# Main_board.net
KiCad netlist of a schematic drawn in EAGLE
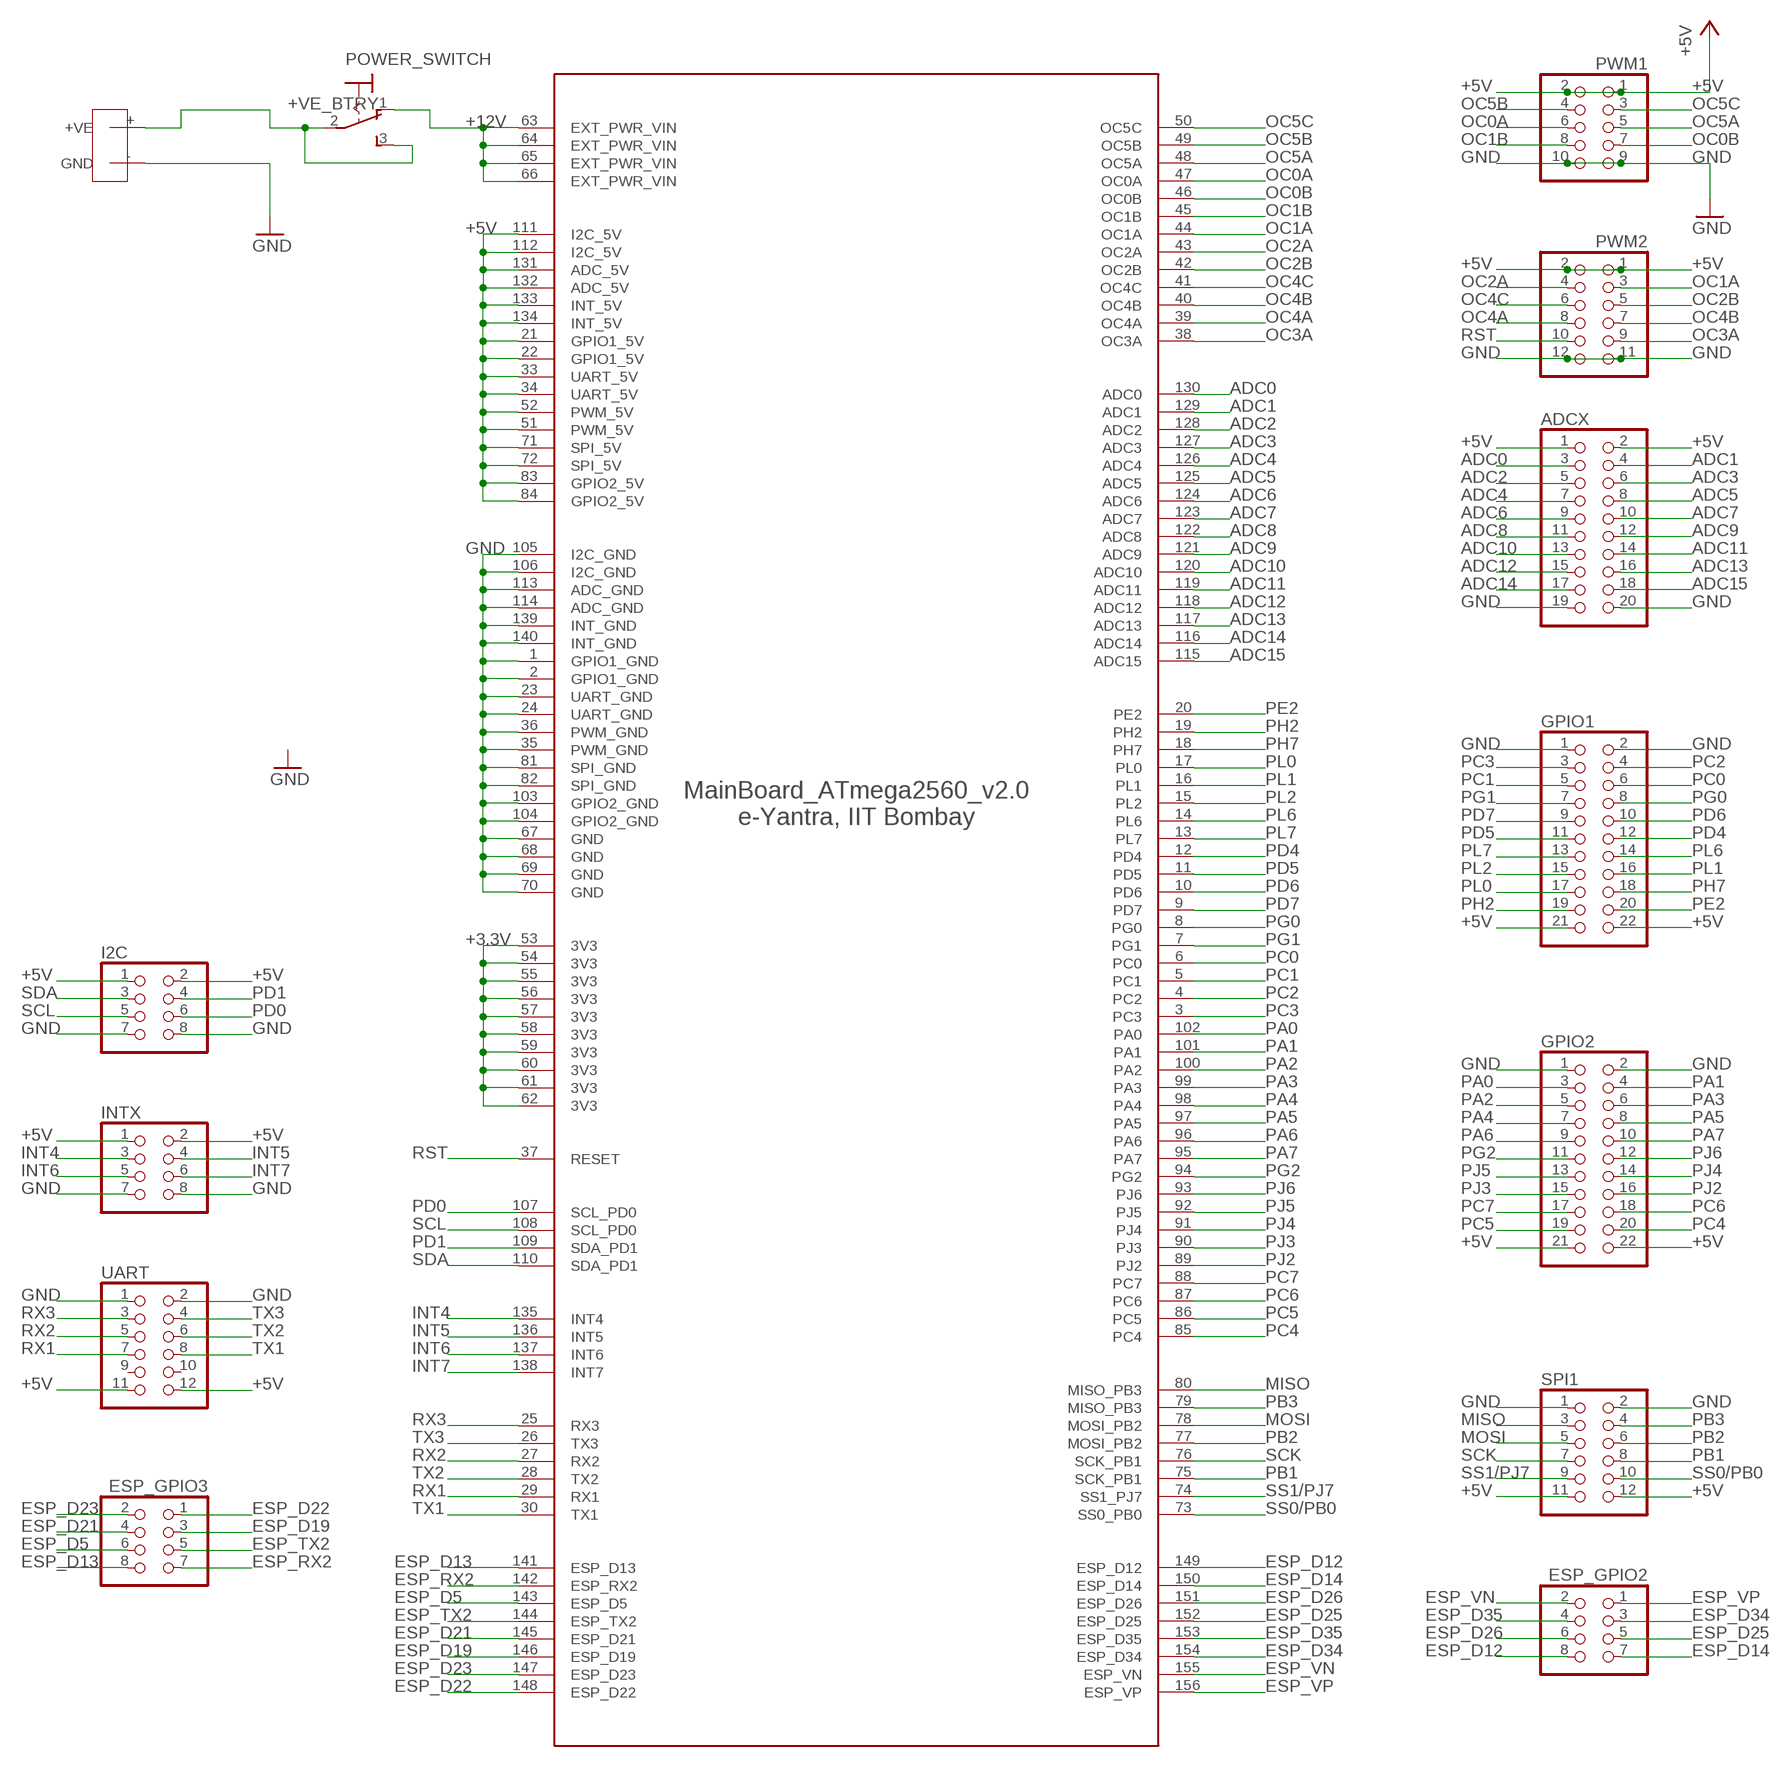
[diagram p0: schematic, sheet 1]
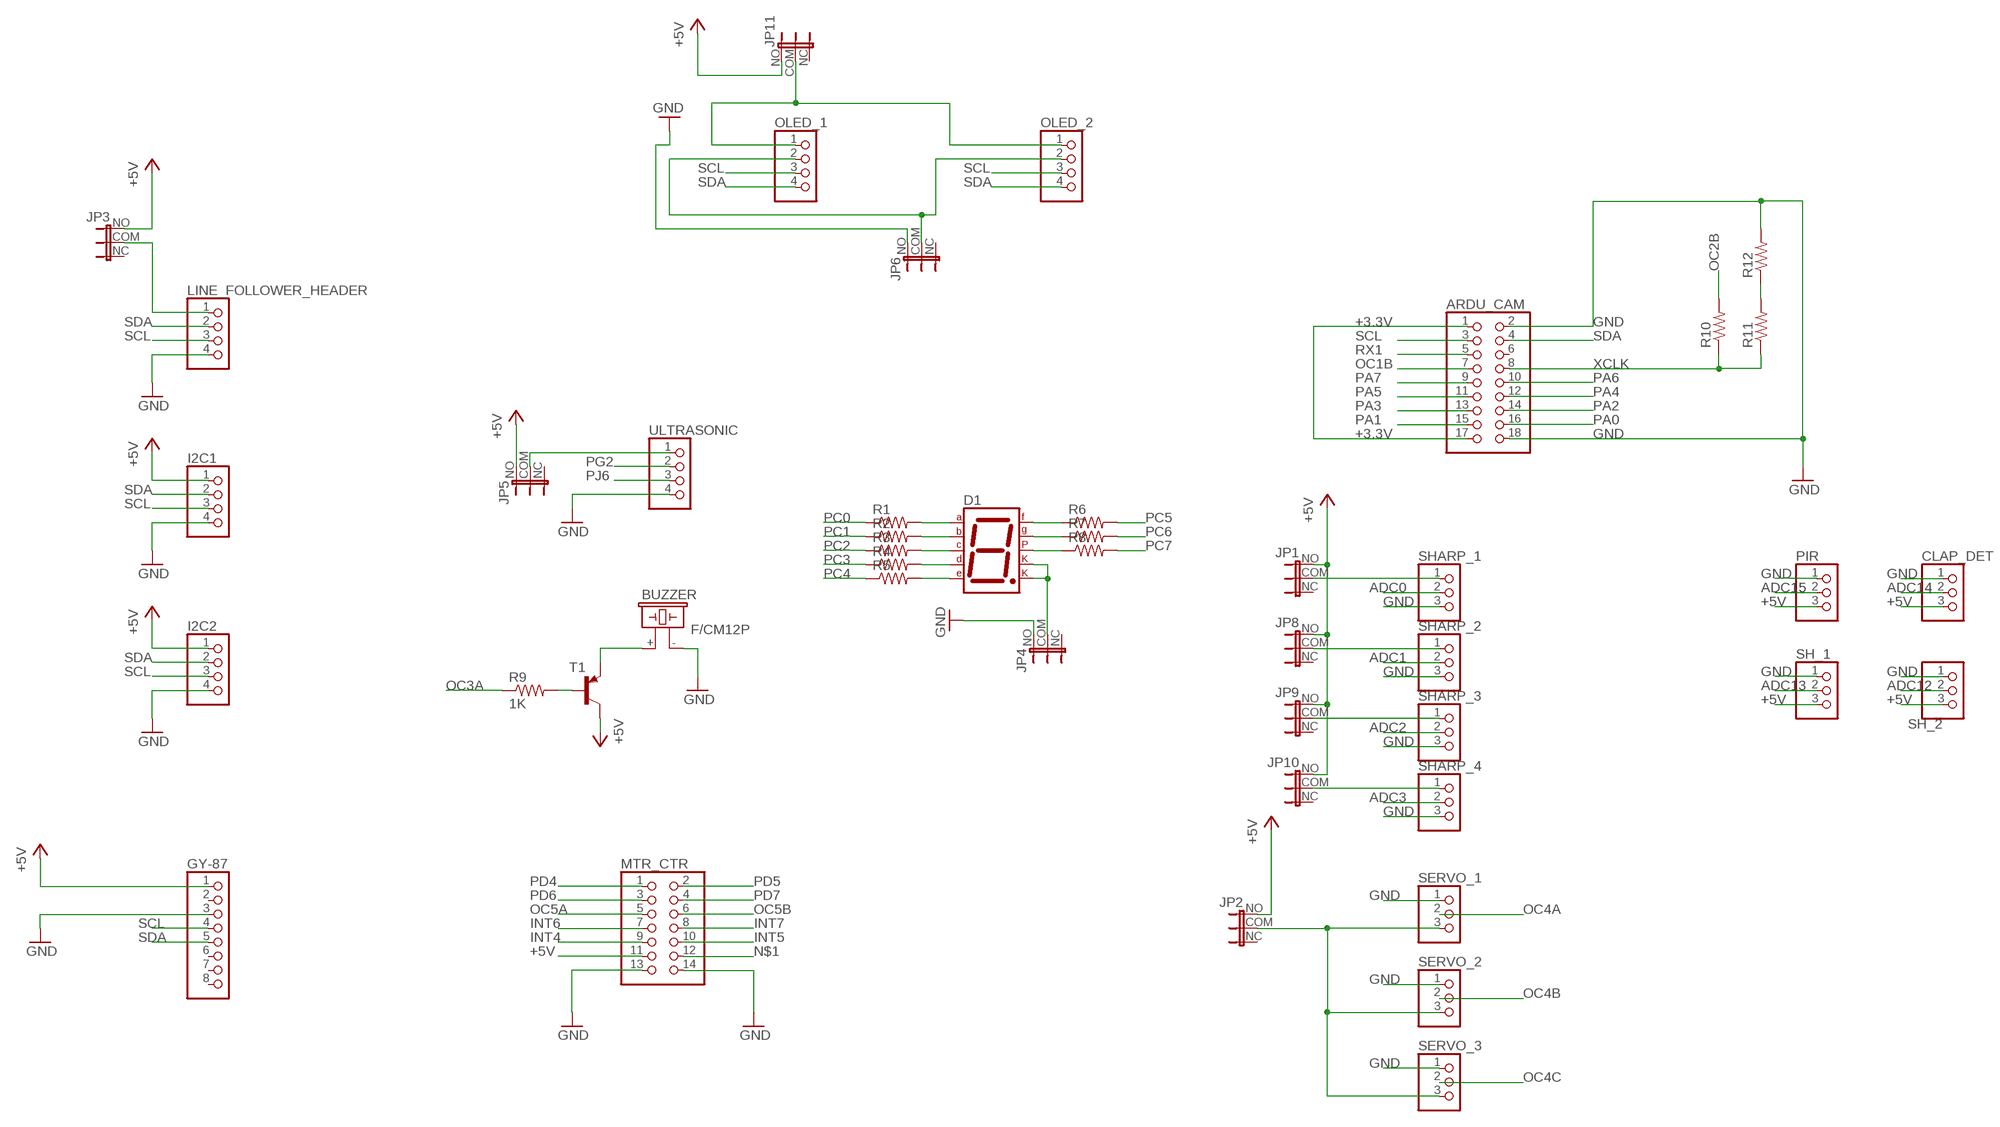
[diagram p1: schematic, sheet 2]

(export (version "E")
  (design (tool "Eeschema 10.0.6"))
  (components
    (comp (ref "ADCX")
      (value "PINHD-2X10")
      (footprint "eagle-import:2X10")
      (libsource (lib "eagle-import") (part "PINHD-2X10"))
    )
    (comp (ref "ESP_GPIO2")
      (value "PINHD-2X4")
      (footprint "eagle-import:2X04")
      (libsource (lib "eagle-import") (part "PINHD-2X4"))
    )
    (comp (ref "ESP_GPIO3")
      (value "PINHD-2X4")
      (footprint "eagle-import:2X04")
      (libsource (lib "eagle-import") (part "PINHD-2X4"))
    )
    (comp (ref "EYFI_MEGA")
      (value "ATMEGA2560_V2.0")
      (footprint "eagle-import:ATMEGA2560_V2.0")
      (libsource (lib "eagle-import") (part "ATMEGA2560_V2.0"))
    )
    (comp (ref "GPIO1")
      (value "PINHD-2X11")
      (footprint "eagle-import:2X11")
      (libsource (lib "eagle-import") (part "PINHD-2X11"))
    )
    (comp (ref "GPIO2")
      (value "PINHD-2X11")
      (footprint "eagle-import:2X11")
      (libsource (lib "eagle-import") (part "PINHD-2X11"))
    )
    (comp (ref "I2C")
      (value "PINHD-2X4")
      (footprint "eagle-import:2X04")
      (libsource (lib "eagle-import") (part "PINHD-2X4"))
    )
    (comp (ref "INTX")
      (value "PINHD-2X4")
      (footprint "eagle-import:2X04")
      (libsource (lib "eagle-import") (part "PINHD-2X4"))
    )
    (comp (ref "POWER_SWITCH")
      (value "M9040P")
      (footprint "eagle-import:M9040P")
      (libsource (lib "eagle-import") (part "M9040P"))
    )
    (comp (ref "PWM1")
      (value "PINHD-2X5")
      (footprint "eagle-import:2X05")
      (libsource (lib "eagle-import") (part "PINHD-2X5"))
    )
    (comp (ref "PWM2")
      (value "PINHD-2X6")
      (footprint "eagle-import:2X06")
      (libsource (lib "eagle-import") (part "PINHD-2X6"))
    )
    (comp (ref "SPI1")
      (value "PINHD-2X6")
      (footprint "eagle-import:2X06")
      (libsource (lib "eagle-import") (part "PINHD-2X6"))
    )
    (comp (ref "U$1")
      (value "DEANS")
      (footprint "eagle-import:DEANS")
      (libsource (lib "eagle-import") (part "DEANS"))
    )
    (comp (ref "UART")
      (value "PINHD-2X6")
      (footprint "eagle-import:2X06")
      (libsource (lib "eagle-import") (part "PINHD-2X6"))
    )
    (comp (ref "ARDU_CAM")
      (value "PINHD-2X9")
      (footprint "eagle-import:2X09")
      (libsource (lib "eagle-import") (part "PINHD-2X9"))
    )
    (comp (ref "BUZZER")
      (value "F/CM12P")
      (footprint "eagle-import:F_CM12P")
      (libsource (lib "eagle-import") (part "F/CM12P"))
    )
    (comp (ref "CLAP_DET")
      (value "PINHD-1X3")
      (footprint "eagle-import:1X03")
      (libsource (lib "eagle-import") (part "pinhead_325_PINHD-1X3"))
    )
    (comp (ref "D1")
      (value "7SEG-CK")
      (footprint "eagle-import:7SEG-13")
      (libsource (lib "eagle-import") (part "7SEG-CK"))
    )
    (comp (ref "GY-87")
      (value "PINHD-1X8")
      (footprint "eagle-import:1X08")
      (libsource (lib "eagle-import") (part "PINHD-1X8"))
    )
    (comp (ref "I2C1")
      (value "PINHD-1X4")
      (footprint "eagle-import:1X04")
      (libsource (lib "eagle-import") (part "PINHD-1X4"))
    )
    (comp (ref "I2C2")
      (value "PINHD-1X4")
      (footprint "eagle-import:1X04")
      (libsource (lib "eagle-import") (part "PINHD-1X4"))
    )
    (comp (ref "JP1")
      (value "JP2E")
      (footprint "eagle-import:JP2")
      (libsource (lib "eagle-import") (part "JP2E"))
    )
    (comp (ref "JP2")
      (value "JP2E")
      (footprint "eagle-import:JP2")
      (libsource (lib "eagle-import") (part "JP2E"))
    )
    (comp (ref "JP3")
      (value "JP2E")
      (footprint "eagle-import:JP2")
      (libsource (lib "eagle-import") (part "JP2E"))
    )
    (comp (ref "JP4")
      (value "JP2E")
      (footprint "eagle-import:JP2")
      (libsource (lib "eagle-import") (part "JP2E"))
    )
    (comp (ref "JP5")
      (value "JP2E")
      (footprint "eagle-import:JP2")
      (libsource (lib "eagle-import") (part "JP2E"))
    )
    (comp (ref "JP6")
      (value "JP2E")
      (footprint "eagle-import:JP2")
      (libsource (lib "eagle-import") (part "JP2E"))
    )
    (comp (ref "JP8")
      (value "JP2E")
      (footprint "eagle-import:JP2")
      (libsource (lib "eagle-import") (part "JP2E"))
    )
    (comp (ref "JP9")
      (value "JP2E")
      (footprint "eagle-import:JP2")
      (libsource (lib "eagle-import") (part "JP2E"))
    )
    (comp (ref "JP10")
      (value "JP2E")
      (footprint "eagle-import:JP2")
      (libsource (lib "eagle-import") (part "JP2E"))
    )
    (comp (ref "JP11")
      (value "JP2E")
      (footprint "eagle-import:JP2")
      (libsource (lib "eagle-import") (part "JP2E"))
    )
    (comp (ref "LINE_FOLLOWER_HEADER")
      (value "PINHD-1X4")
      (footprint "eagle-import:1X04")
      (libsource (lib "eagle-import") (part "PINHD-1X4"))
    )
    (comp (ref "MTR_CTR")
      (value "PINHD-2X7")
      (footprint "eagle-import:2X07")
      (libsource (lib "eagle-import") (part "PINHD-2X7"))
    )
    (comp (ref "OLED_1")
      (value "PINHD-1X4")
      (footprint "eagle-import:1X04")
      (libsource (lib "eagle-import") (part "PINHD-1X4"))
    )
    (comp (ref "OLED_2")
      (value "PINHD-1X4")
      (footprint "eagle-import:1X04")
      (libsource (lib "eagle-import") (part "PINHD-1X4"))
    )
    (comp (ref "PIR")
      (value "PINHD-1X3")
      (footprint "eagle-import:1X03")
      (libsource (lib "eagle-import") (part "pinhead_325_PINHD-1X3"))
    )
    (comp (ref "R1")
      (value "R-US_R1206")
      (footprint "eagle-import:R1206")
      (libsource (lib "eagle-import") (part "R-US_R1206"))
    )
    (comp (ref "R2")
      (value "R-US_R1206")
      (footprint "eagle-import:R1206")
      (libsource (lib "eagle-import") (part "R-US_R1206"))
    )
    (comp (ref "R3")
      (value "R-US_R1206")
      (footprint "eagle-import:R1206")
      (libsource (lib "eagle-import") (part "R-US_R1206"))
    )
    (comp (ref "R4")
      (value "R-US_R1206")
      (footprint "eagle-import:R1206")
      (libsource (lib "eagle-import") (part "R-US_R1206"))
    )
    (comp (ref "R5")
      (value "R-US_R1206")
      (footprint "eagle-import:R1206")
      (libsource (lib "eagle-import") (part "R-US_R1206"))
    )
    (comp (ref "R6")
      (value "R-US_R1206")
      (footprint "eagle-import:R1206")
      (libsource (lib "eagle-import") (part "R-US_R1206"))
    )
    (comp (ref "R7")
      (value "R-US_R1206")
      (footprint "eagle-import:R1206")
      (libsource (lib "eagle-import") (part "R-US_R1206"))
    )
    (comp (ref "R8")
      (value "R-US_R1206")
      (footprint "eagle-import:R1206")
      (libsource (lib "eagle-import") (part "R-US_R1206"))
    )
    (comp (ref "R9")
      (value "1K")
      (footprint "eagle-import:R1206")
      (libsource (lib "eagle-import") (part "R-US_R1206"))
    )
    (comp (ref "R10")
      (value "R-US_R1206")
      (footprint "eagle-import:R1206")
      (libsource (lib "eagle-import") (part "R-US_R1206"))
    )
    (comp (ref "R11")
      (value "R-US_R1206")
      (footprint "eagle-import:R1206")
      (libsource (lib "eagle-import") (part "R-US_R1206"))
    )
    (comp (ref "R12")
      (value "R-US_R1206")
      (footprint "eagle-import:R1206")
      (libsource (lib "eagle-import") (part "R-US_R1206"))
    )
    (comp (ref "SERVO_1")
      (value "PINHD-1X3")
      (footprint "eagle-import:1X03")
      (libsource (lib "eagle-import") (part "pinhead_325_PINHD-1X3"))
    )
    (comp (ref "SERVO_2")
      (value "PINHD-1X3")
      (footprint "eagle-import:1X03")
      (libsource (lib "eagle-import") (part "pinhead_325_PINHD-1X3"))
    )
    (comp (ref "SERVO_3")
      (value "PINHD-1X3")
      (footprint "eagle-import:1X03")
      (libsource (lib "eagle-import") (part "pinhead_325_PINHD-1X3"))
    )
    (comp (ref "SHARP_1")
      (value "PINHD-1X3")
      (footprint "eagle-import:1X03")
      (libsource (lib "eagle-import") (part "PINHD-1X3"))
    )
    (comp (ref "SHARP_2")
      (value "PINHD-1X3")
      (footprint "eagle-import:1X03")
      (libsource (lib "eagle-import") (part "PINHD-1X3"))
    )
    (comp (ref "SHARP_3")
      (value "PINHD-1X3")
      (footprint "eagle-import:1X03")
      (libsource (lib "eagle-import") (part "PINHD-1X3"))
    )
    (comp (ref "SHARP_4")
      (value "PINHD-1X3")
      (footprint "eagle-import:1X03")
      (libsource (lib "eagle-import") (part "PINHD-1X3"))
    )
    (comp (ref "SH_1")
      (value "PINHD-1X3")
      (footprint "eagle-import:1X03")
      (libsource (lib "eagle-import") (part "pinhead_325_PINHD-1X3"))
    )
    (comp (ref "SH_2")
      (value "PINHD-1X3")
      (footprint "eagle-import:1X03")
      (libsource (lib "eagle-import") (part "pinhead_325_PINHD-1X3"))
    )
    (comp (ref "T1")
      (value "BC807-16-PNP-SOT23-BEC")
      (footprint "eagle-import:SOT23-BEC")
      (libsource (lib "eagle-import") (part "-PNP-SOT23-BECBC807-16"))
    )
    (comp (ref "ULTRASONIC")
      (value "PINHD-1X4")
      (footprint "eagle-import:1X04")
      (libsource (lib "eagle-import") (part "PINHD-1X4"))
    )
  )
  (nets
    (net (code "1") (name "+3.3V") (class "Default")
      (node (ref "ARDU_CAM") (pin "1") (pinfunction "1_1") (pintype "passive"))
      (node (ref "ARDU_CAM") (pin "17") (pinfunction "17_17") (pintype "passive"))
      (node (ref "EYFI_MEGA") (pin "53") (pinfunction "3V3_53") (pintype "power_in"))
      (node (ref "EYFI_MEGA") (pin "54") (pinfunction "3V3_54") (pintype "power_in"))
      (node (ref "EYFI_MEGA") (pin "55") (pinfunction "3V3_55") (pintype "power_in"))
      (node (ref "EYFI_MEGA") (pin "56") (pinfunction "3V3_56") (pintype "power_in"))
      (node (ref "EYFI_MEGA") (pin "57") (pinfunction "3V3_57") (pintype "power_in"))
      (node (ref "EYFI_MEGA") (pin "58") (pinfunction "3V3_58") (pintype "power_in"))
      (node (ref "EYFI_MEGA") (pin "59") (pinfunction "3V3_59") (pintype "power_in"))
      (node (ref "EYFI_MEGA") (pin "60") (pinfunction "3V3_60") (pintype "power_in"))
      (node (ref "EYFI_MEGA") (pin "61") (pinfunction "3V3_61") (pintype "power_in"))
      (node (ref "EYFI_MEGA") (pin "62") (pinfunction "3V3_62") (pintype "power_in"))
    )
    (net (code "2") (name "+5V") (class "Default")
      (node (ref "ADCX") (pin "1") (pinfunction "1_1") (pintype "passive"))
      (node (ref "ADCX") (pin "2") (pinfunction "2_2") (pintype "passive"))
      (node (ref "CLAP_DET") (pin "3") (pinfunction "3_3") (pintype "passive"))
      (node (ref "EYFI_MEGA") (pin "111") (pinfunction "I2C_5V_111") (pintype "power_in"))
      (node (ref "EYFI_MEGA") (pin "112") (pinfunction "I2C_5V_112") (pintype "power_in"))
      (node (ref "EYFI_MEGA") (pin "131") (pinfunction "ADC_5V_131") (pintype "power_in"))
      (node (ref "EYFI_MEGA") (pin "132") (pinfunction "ADC_5V_132") (pintype "power_in"))
      (node (ref "EYFI_MEGA") (pin "133") (pinfunction "INT_5V_133") (pintype "power_in"))
      (node (ref "EYFI_MEGA") (pin "134") (pinfunction "INT_5V_134") (pintype "power_in"))
      (node (ref "EYFI_MEGA") (pin "21") (pinfunction "GPIO1_5V_21") (pintype "power_in"))
      (node (ref "EYFI_MEGA") (pin "22") (pinfunction "GPIO1_5V_22") (pintype "power_in"))
      (node (ref "EYFI_MEGA") (pin "33") (pinfunction "UART_5V_33") (pintype "power_in"))
      (node (ref "EYFI_MEGA") (pin "34") (pinfunction "UART_5V_34") (pintype "power_in"))
      (node (ref "EYFI_MEGA") (pin "51") (pinfunction "PWM_5V_51") (pintype "power_in"))
      (node (ref "EYFI_MEGA") (pin "52") (pinfunction "PWM_5V_52") (pintype "power_in"))
      (node (ref "EYFI_MEGA") (pin "71") (pinfunction "SPI_5V_71") (pintype "power_in"))
      (node (ref "EYFI_MEGA") (pin "72") (pinfunction "SPI_5V_72") (pintype "power_in"))
      (node (ref "EYFI_MEGA") (pin "83") (pinfunction "GPIO2_5V_83") (pintype "power_in"))
      (node (ref "EYFI_MEGA") (pin "84") (pinfunction "GPIO2_5V_84") (pintype "power_in"))
      (node (ref "GPIO1") (pin "21") (pinfunction "21_21") (pintype "passive"))
      (node (ref "GPIO1") (pin "22") (pinfunction "22_22") (pintype "passive"))
      (node (ref "GPIO2") (pin "21") (pinfunction "21_21") (pintype "passive"))
      (node (ref "GPIO2") (pin "22") (pinfunction "22_22") (pintype "passive"))
      (node (ref "GY-87") (pin "1") (pinfunction "1_1") (pintype "passive"))
      (node (ref "I2C") (pin "1") (pinfunction "1_1") (pintype "passive"))
      (node (ref "I2C") (pin "2") (pinfunction "2_2") (pintype "passive"))
      (node (ref "I2C1") (pin "1") (pinfunction "1_1") (pintype "passive"))
      (node (ref "I2C2") (pin "1") (pinfunction "1_1") (pintype "passive"))
      (node (ref "INTX") (pin "1") (pinfunction "1_1") (pintype "passive"))
      (node (ref "INTX") (pin "2") (pinfunction "2_2") (pintype "passive"))
      (node (ref "JP1") (pin "NO") (pinfunction "1_NO") (pintype "passive"))
      (node (ref "JP10") (pin "NO") (pinfunction "1_NO") (pintype "passive"))
      (node (ref "JP11") (pin "NO") (pinfunction "1_NO") (pintype "passive"))
      (node (ref "JP2") (pin "NO") (pinfunction "1_NO") (pintype "passive"))
      (node (ref "JP3") (pin "NO") (pinfunction "1_NO") (pintype "passive"))
      (node (ref "JP5") (pin "NO") (pinfunction "1_NO") (pintype "passive"))
      (node (ref "JP8") (pin "NO") (pinfunction "1_NO") (pintype "passive"))
      (node (ref "JP9") (pin "NO") (pinfunction "1_NO") (pintype "passive"))
      (node (ref "MTR_CTR") (pin "11") (pinfunction "11_11") (pintype "passive"))
      (node (ref "PIR") (pin "3") (pinfunction "3_3") (pintype "passive"))
      (node (ref "PWM1") (pin "1") (pinfunction "1_1") (pintype "passive"))
      (node (ref "PWM1") (pin "2") (pinfunction "2_2") (pintype "passive"))
      (node (ref "PWM2") (pin "1") (pinfunction "1_1") (pintype "passive"))
      (node (ref "PWM2") (pin "2") (pinfunction "2_2") (pintype "passive"))
      (node (ref "SH_1") (pin "3") (pinfunction "3_3") (pintype "passive"))
      (node (ref "SH_2") (pin "3") (pinfunction "3_3") (pintype "passive"))
      (node (ref "SPI1") (pin "11") (pinfunction "11_11") (pintype "passive"))
      (node (ref "SPI1") (pin "12") (pinfunction "12_12") (pintype "passive"))
      (node (ref "T1") (pin "C") (pinfunction "C_C") (pintype "passive"))
      (node (ref "UART") (pin "11") (pinfunction "11_11") (pintype "passive"))
      (node (ref "UART") (pin "12") (pinfunction "12_12") (pintype "passive"))
    )
    (net (code "3") (name "+12V") (class "Default")
      (node (ref "EYFI_MEGA") (pin "63") (pinfunction "EXT_PWR_VIN_63") (pintype "power_in"))
      (node (ref "EYFI_MEGA") (pin "64") (pinfunction "EXT_PWR_VIN_64") (pintype "power_in"))
      (node (ref "EYFI_MEGA") (pin "65") (pinfunction "EXT_PWR_VIN_65") (pintype "power_in"))
      (node (ref "EYFI_MEGA") (pin "66") (pinfunction "EXT_PWR_VIN_66") (pintype "power_in"))
      (node (ref "POWER_SWITCH") (pin "1") (pinfunction "O_1") (pintype "passive"))
    )
    (net (code "4") (name "+VE_BTRY") (class "Default")
      (node (ref "POWER_SWITCH") (pin "2") (pinfunction "P_2") (pintype "passive"))
      (node (ref "POWER_SWITCH") (pin "3") (pinfunction "S_3") (pintype "passive"))
      (node (ref "U$1") (pin "+") (pinfunction "+VE_+") (pintype "bidirectional"))
    )
    (net (code "5") (name "ADC0") (class "Default")
      (node (ref "ADCX") (pin "3") (pinfunction "3_3") (pintype "passive"))
      (node (ref "EYFI_MEGA") (pin "130") (pinfunction "ADC0_130") (pintype "bidirectional"))
      (node (ref "SHARP_1") (pin "2") (pinfunction "2_2") (pintype "passive"))
    )
    (net (code "6") (name "ADC1") (class "Default")
      (node (ref "ADCX") (pin "4") (pinfunction "4_4") (pintype "passive"))
      (node (ref "EYFI_MEGA") (pin "129") (pinfunction "ADC1_129") (pintype "bidirectional"))
      (node (ref "SHARP_2") (pin "2") (pinfunction "2_2") (pintype "passive"))
    )
    (net (code "7") (name "ADC2") (class "Default")
      (node (ref "ADCX") (pin "5") (pinfunction "5_5") (pintype "passive"))
      (node (ref "EYFI_MEGA") (pin "128") (pinfunction "ADC2_128") (pintype "bidirectional"))
      (node (ref "SHARP_3") (pin "2") (pinfunction "2_2") (pintype "passive"))
    )
    (net (code "8") (name "ADC3") (class "Default")
      (node (ref "ADCX") (pin "6") (pinfunction "6_6") (pintype "passive"))
      (node (ref "EYFI_MEGA") (pin "127") (pinfunction "ADC3_127") (pintype "bidirectional"))
      (node (ref "SHARP_4") (pin "2") (pinfunction "2_2") (pintype "passive"))
    )
    (net (code "9") (name "ADC4") (class "Default")
      (node (ref "ADCX") (pin "7") (pinfunction "7_7") (pintype "passive"))
      (node (ref "EYFI_MEGA") (pin "126") (pinfunction "ADC4_126") (pintype "bidirectional"))
    )
    (net (code "10") (name "ADC5") (class "Default")
      (node (ref "ADCX") (pin "8") (pinfunction "8_8") (pintype "passive"))
      (node (ref "EYFI_MEGA") (pin "125") (pinfunction "ADC5_125") (pintype "bidirectional"))
    )
    (net (code "11") (name "ADC6") (class "Default")
      (node (ref "ADCX") (pin "9") (pinfunction "9_9") (pintype "passive"))
      (node (ref "EYFI_MEGA") (pin "124") (pinfunction "ADC6_124") (pintype "bidirectional"))
    )
    (net (code "12") (name "ADC7") (class "Default")
      (node (ref "ADCX") (pin "10") (pinfunction "10_10") (pintype "passive"))
      (node (ref "EYFI_MEGA") (pin "123") (pinfunction "ADC7_123") (pintype "bidirectional"))
    )
    (net (code "13") (name "ADC8") (class "Default")
      (node (ref "ADCX") (pin "11") (pinfunction "11_11") (pintype "passive"))
      (node (ref "EYFI_MEGA") (pin "122") (pinfunction "ADC8_122") (pintype "bidirectional"))
    )
    (net (code "14") (name "ADC9") (class "Default")
      (node (ref "ADCX") (pin "12") (pinfunction "12_12") (pintype "passive"))
      (node (ref "EYFI_MEGA") (pin "121") (pinfunction "ADC9_121") (pintype "bidirectional"))
    )
    (net (code "15") (name "ADC10") (class "Default")
      (node (ref "ADCX") (pin "13") (pinfunction "13_13") (pintype "passive"))
      (node (ref "EYFI_MEGA") (pin "120") (pinfunction "ADC10_120") (pintype "bidirectional"))
    )
    (net (code "16") (name "ADC11") (class "Default")
      (node (ref "ADCX") (pin "14") (pinfunction "14_14") (pintype "passive"))
      (node (ref "EYFI_MEGA") (pin "119") (pinfunction "ADC11_119") (pintype "bidirectional"))
    )
    (net (code "17") (name "ADC12") (class "Default")
      (node (ref "ADCX") (pin "15") (pinfunction "15_15") (pintype "passive"))
      (node (ref "EYFI_MEGA") (pin "118") (pinfunction "ADC12_118") (pintype "bidirectional"))
      (node (ref "SH_2") (pin "2") (pinfunction "2_2") (pintype "passive"))
    )
    (net (code "18") (name "ADC13") (class "Default")
      (node (ref "ADCX") (pin "16") (pinfunction "16_16") (pintype "passive"))
      (node (ref "EYFI_MEGA") (pin "117") (pinfunction "ADC13_117") (pintype "bidirectional"))
      (node (ref "SH_1") (pin "2") (pinfunction "2_2") (pintype "passive"))
    )
    (net (code "19") (name "ADC14") (class "Default")
      (node (ref "ADCX") (pin "17") (pinfunction "17_17") (pintype "passive"))
      (node (ref "CLAP_DET") (pin "2") (pinfunction "2_2") (pintype "passive"))
      (node (ref "EYFI_MEGA") (pin "116") (pinfunction "ADC14_116") (pintype "bidirectional"))
    )
    (net (code "20") (name "ADC15") (class "Default")
      (node (ref "ADCX") (pin "18") (pinfunction "18_18") (pintype "passive"))
      (node (ref "EYFI_MEGA") (pin "115") (pinfunction "ADC15_115") (pintype "bidirectional"))
      (node (ref "PIR") (pin "2") (pinfunction "2_2") (pintype "passive"))
    )
    (net (code "21") (name "ESP_D5") (class "Default")
      (node (ref "ESP_GPIO3") (pin "6") (pinfunction "6_6") (pintype "passive"))
      (node (ref "EYFI_MEGA") (pin "143") (pinfunction "ESP_D5_143") (pintype "bidirectional"))
    )
    (net (code "22") (name "ESP_D12") (class "Default")
      (node (ref "ESP_GPIO2") (pin "8") (pinfunction "8_8") (pintype "passive"))
      (node (ref "EYFI_MEGA") (pin "149") (pinfunction "ESP_D12_149") (pintype "bidirectional"))
    )
    (net (code "23") (name "ESP_D13") (class "Default")
      (node (ref "ESP_GPIO3") (pin "8") (pinfunction "8_8") (pintype "passive"))
      (node (ref "EYFI_MEGA") (pin "141") (pinfunction "ESP_D13_141") (pintype "bidirectional"))
    )
    (net (code "24") (name "ESP_D14") (class "Default")
      (node (ref "ESP_GPIO2") (pin "7") (pinfunction "7_7") (pintype "passive"))
      (node (ref "EYFI_MEGA") (pin "150") (pinfunction "ESP_D14_150") (pintype "bidirectional"))
    )
    (net (code "25") (name "ESP_D19") (class "Default")
      (node (ref "ESP_GPIO3") (pin "3") (pinfunction "3_3") (pintype "passive"))
      (node (ref "EYFI_MEGA") (pin "146") (pinfunction "ESP_D19_146") (pintype "bidirectional"))
    )
    (net (code "26") (name "ESP_D21") (class "Default")
      (node (ref "ESP_GPIO3") (pin "4") (pinfunction "4_4") (pintype "passive"))
      (node (ref "EYFI_MEGA") (pin "145") (pinfunction "ESP_D21_145") (pintype "bidirectional"))
    )
    (net (code "27") (name "ESP_D22") (class "Default")
      (node (ref "ESP_GPIO3") (pin "1") (pinfunction "1_1") (pintype "passive"))
      (node (ref "EYFI_MEGA") (pin "148") (pinfunction "ESP_D22_148") (pintype "bidirectional"))
    )
    (net (code "28") (name "ESP_D23") (class "Default")
      (node (ref "ESP_GPIO3") (pin "2") (pinfunction "2_2") (pintype "passive"))
      (node (ref "EYFI_MEGA") (pin "147") (pinfunction "ESP_D23_147") (pintype "bidirectional"))
    )
    (net (code "29") (name "ESP_D25") (class "Default")
      (node (ref "ESP_GPIO2") (pin "5") (pinfunction "5_5") (pintype "passive"))
      (node (ref "EYFI_MEGA") (pin "152") (pinfunction "ESP_D25_152") (pintype "bidirectional"))
    )
    (net (code "30") (name "ESP_D26") (class "Default")
      (node (ref "ESP_GPIO2") (pin "6") (pinfunction "6_6") (pintype "passive"))
      (node (ref "EYFI_MEGA") (pin "151") (pinfunction "ESP_D26_151") (pintype "bidirectional"))
    )
    (net (code "31") (name "ESP_D34") (class "Default")
      (node (ref "ESP_GPIO2") (pin "3") (pinfunction "3_3") (pintype "passive"))
      (node (ref "EYFI_MEGA") (pin "154") (pinfunction "ESP_D34_154") (pintype "bidirectional"))
    )
    (net (code "32") (name "ESP_D35") (class "Default")
      (node (ref "ESP_GPIO2") (pin "4") (pinfunction "4_4") (pintype "passive"))
      (node (ref "EYFI_MEGA") (pin "153") (pinfunction "ESP_D35_153") (pintype "bidirectional"))
    )
    (net (code "33") (name "ESP_RX2") (class "Default")
      (node (ref "ESP_GPIO3") (pin "7") (pinfunction "7_7") (pintype "passive"))
      (node (ref "EYFI_MEGA") (pin "142") (pinfunction "ESP_RX2_142") (pintype "bidirectional"))
    )
    (net (code "34") (name "ESP_TX2") (class "Default")
      (node (ref "ESP_GPIO3") (pin "5") (pinfunction "5_5") (pintype "passive"))
      (node (ref "EYFI_MEGA") (pin "144") (pinfunction "ESP_TX2_144") (pintype "bidirectional"))
    )
    (net (code "35") (name "ESP_VN") (class "Default")
      (node (ref "ESP_GPIO2") (pin "2") (pinfunction "2_2") (pintype "passive"))
      (node (ref "EYFI_MEGA") (pin "155") (pinfunction "ESP_VN_155") (pintype "bidirectional"))
    )
    (net (code "36") (name "ESP_VP") (class "Default")
      (node (ref "ESP_GPIO2") (pin "1") (pinfunction "1_1") (pintype "passive"))
      (node (ref "EYFI_MEGA") (pin "156") (pinfunction "ESP_VP_156") (pintype "bidirectional"))
    )
    (net (code "37") (name "GND") (class "Default")
      (node (ref "ADCX") (pin "19") (pinfunction "19_19") (pintype "passive"))
      (node (ref "ADCX") (pin "20") (pinfunction "20_20") (pintype "passive"))
      (node (ref "ARDU_CAM") (pin "18") (pinfunction "18_18") (pintype "passive"))
      (node (ref "ARDU_CAM") (pin "2") (pinfunction "2_2") (pintype "passive"))
      (node (ref "BUZZER") (pin "-") (pinfunction "2_-") (pintype "passive"))
      (node (ref "CLAP_DET") (pin "1") (pinfunction "1_1") (pintype "passive"))
      (node (ref "EYFI_MEGA") (pin "1") (pinfunction "GPIO1_GND_1") (pintype "power_in"))
      (node (ref "EYFI_MEGA") (pin "103") (pinfunction "GPIO2_GND_103") (pintype "power_in"))
      (node (ref "EYFI_MEGA") (pin "104") (pinfunction "GPIO2_GND_104") (pintype "power_in"))
      (node (ref "EYFI_MEGA") (pin "105") (pinfunction "I2C_GND_105") (pintype "power_in"))
      (node (ref "EYFI_MEGA") (pin "106") (pinfunction "I2C_GND_106") (pintype "power_in"))
      (node (ref "EYFI_MEGA") (pin "113") (pinfunction "ADC_GND_113") (pintype "power_in"))
      (node (ref "EYFI_MEGA") (pin "114") (pinfunction "ADC_GND_114") (pintype "power_in"))
      (node (ref "EYFI_MEGA") (pin "139") (pinfunction "INT_GND_139") (pintype "power_in"))
      (node (ref "EYFI_MEGA") (pin "140") (pinfunction "INT_GND_140") (pintype "power_in"))
      (node (ref "EYFI_MEGA") (pin "2") (pinfunction "GPIO1_GND_2") (pintype "power_in"))
      (node (ref "EYFI_MEGA") (pin "23") (pinfunction "UART_GND_23") (pintype "power_in"))
      (node (ref "EYFI_MEGA") (pin "24") (pinfunction "UART_GND_24") (pintype "power_in"))
      (node (ref "EYFI_MEGA") (pin "35") (pinfunction "PWM_GND_35") (pintype "power_in"))
      (node (ref "EYFI_MEGA") (pin "36") (pinfunction "PWM_GND_36") (pintype "power_in"))
      (node (ref "EYFI_MEGA") (pin "67") (pinfunction "GND_67") (pintype "power_in"))
      (node (ref "EYFI_MEGA") (pin "68") (pinfunction "GND_68") (pintype "power_in"))
      (node (ref "EYFI_MEGA") (pin "69") (pinfunction "GND_69") (pintype "power_in"))
      (node (ref "EYFI_MEGA") (pin "70") (pinfunction "GND_70") (pintype "power_in"))
      (node (ref "EYFI_MEGA") (pin "81") (pinfunction "SPI_GND_81") (pintype "power_in"))
      (node (ref "EYFI_MEGA") (pin "82") (pinfunction "SPI_GND_82") (pintype "power_in"))
      (node (ref "GPIO1") (pin "1") (pinfunction "1_1") (pintype "passive"))
      (node (ref "GPIO1") (pin "2") (pinfunction "2_2") (pintype "passive"))
      (node (ref "GPIO2") (pin "1") (pinfunction "1_1") (pintype "passive"))
      (node (ref "GPIO2") (pin "2") (pinfunction "2_2") (pintype "passive"))
      (node (ref "GY-87") (pin "3") (pinfunction "3_3") (pintype "passive"))
      (node (ref "I2C") (pin "7") (pinfunction "7_7") (pintype "passive"))
      (node (ref "I2C") (pin "8") (pinfunction "8_8") (pintype "passive"))
      (node (ref "I2C1") (pin "4") (pinfunction "4_4") (pintype "passive"))
      (node (ref "I2C2") (pin "4") (pinfunction "4_4") (pintype "passive"))
      (node (ref "INTX") (pin "7") (pinfunction "7_7") (pintype "passive"))
      (node (ref "INTX") (pin "8") (pinfunction "8_8") (pintype "passive"))
      (node (ref "JP4") (pin "NO") (pinfunction "1_NO") (pintype "passive"))
      (node (ref "JP6") (pin "NO") (pinfunction "1_NO") (pintype "passive"))
      (node (ref "LINE_FOLLOWER_HEADER") (pin "4") (pinfunction "4_4") (pintype "passive"))
      (node (ref "MTR_CTR") (pin "13") (pinfunction "13_13") (pintype "passive"))
      (node (ref "MTR_CTR") (pin "14") (pinfunction "14_14") (pintype "passive"))
      (node (ref "PIR") (pin "1") (pinfunction "1_1") (pintype "passive"))
      (node (ref "PWM1") (pin "10") (pinfunction "10_10") (pintype "passive"))
      (node (ref "PWM1") (pin "9") (pinfunction "9_9") (pintype "passive"))
      (node (ref "PWM2") (pin "11") (pinfunction "11_11") (pintype "passive"))
      (node (ref "PWM2") (pin "12") (pinfunction "12_12") (pintype "passive"))
      (node (ref "R12") (pin "2") (pinfunction "2_2") (pintype "passive"))
      (node (ref "SERVO_1") (pin "1") (pinfunction "1_1") (pintype "passive"))
      (node (ref "SERVO_2") (pin "1") (pinfunction "1_1") (pintype "passive"))
      (node (ref "SERVO_3") (pin "1") (pinfunction "1_1") (pintype "passive"))
      (node (ref "SHARP_1") (pin "3") (pinfunction "3_3") (pintype "passive"))
      (node (ref "SHARP_2") (pin "3") (pinfunction "3_3") (pintype "passive"))
      (node (ref "SHARP_3") (pin "3") (pinfunction "3_3") (pintype "passive"))
      (node (ref "SHARP_4") (pin "3") (pinfunction "3_3") (pintype "passive"))
      (node (ref "SH_1") (pin "1") (pinfunction "1_1") (pintype "passive"))
      (node (ref "SH_2") (pin "1") (pinfunction "1_1") (pintype "passive"))
      (node (ref "SPI1") (pin "1") (pinfunction "1_1") (pintype "passive"))
      (node (ref "SPI1") (pin "2") (pinfunction "2_2") (pintype "passive"))
      (node (ref "U$1") (pin "-") (pinfunction "GND_-") (pintype "bidirectional"))
      (node (ref "UART") (pin "1") (pinfunction "1_1") (pintype "passive"))
      (node (ref "UART") (pin "2") (pinfunction "2_2") (pintype "passive"))
      (node (ref "ULTRASONIC") (pin "4") (pinfunction "4_4") (pintype "passive"))
    )
    (net (code "38") (name "INT4") (class "Default")
      (node (ref "EYFI_MEGA") (pin "135") (pinfunction "INT4_135") (pintype "bidirectional"))
      (node (ref "INTX") (pin "3") (pinfunction "3_3") (pintype "passive"))
      (node (ref "MTR_CTR") (pin "9") (pinfunction "9_9") (pintype "passive"))
    )
    (net (code "39") (name "INT5") (class "Default")
      (node (ref "EYFI_MEGA") (pin "136") (pinfunction "INT5_136") (pintype "bidirectional"))
      (node (ref "INTX") (pin "4") (pinfunction "4_4") (pintype "passive"))
      (node (ref "MTR_CTR") (pin "10") (pinfunction "10_10") (pintype "passive"))
    )
    (net (code "40") (name "INT6") (class "Default")
      (node (ref "EYFI_MEGA") (pin "137") (pinfunction "INT6_137") (pintype "bidirectional"))
      (node (ref "INTX") (pin "5") (pinfunction "5_5") (pintype "passive"))
      (node (ref "MTR_CTR") (pin "7") (pinfunction "7_7") (pintype "passive"))
    )
    (net (code "41") (name "INT7") (class "Default")
      (node (ref "EYFI_MEGA") (pin "138") (pinfunction "INT7_138") (pintype "bidirectional"))
      (node (ref "INTX") (pin "6") (pinfunction "6_6") (pintype "passive"))
      (node (ref "MTR_CTR") (pin "8") (pinfunction "8_8") (pintype "passive"))
    )
    (net (code "42") (name "MISO") (class "Default")
      (node (ref "EYFI_MEGA") (pin "80") (pinfunction "MISO_PB3_80") (pintype "bidirectional"))
      (node (ref "SPI1") (pin "3") (pinfunction "3_3") (pintype "passive"))
    )
    (net (code "43") (name "MOSI") (class "Default")
      (node (ref "EYFI_MEGA") (pin "78") (pinfunction "MOSI_PB2_78") (pintype "bidirectional"))
      (node (ref "SPI1") (pin "5") (pinfunction "5_5") (pintype "passive"))
    )
    (net (code "44") (name "N$1") (class "Default")
      (node (ref "MTR_CTR") (pin "12") (pinfunction "12_12") (pintype "passive"))
    )
    (net (code "45") (name "Net-(BUZZER-1)") (class "Default")
      (node (ref "BUZZER") (pin "+") (pinfunction "1_+") (pintype "passive"))
      (node (ref "T1") (pin "E") (pinfunction "E_E") (pintype "passive"))
    )
    (net (code "46") (name "Net-(D1-A)") (class "Default")
      (node (ref "D1") (pin "7") (pinfunction "A_7") (pintype "passive"))
      (node (ref "R1") (pin "2") (pinfunction "2_2") (pintype "passive"))
    )
    (net (code "47") (name "Net-(D1-B)") (class "Default")
      (node (ref "D1") (pin "6") (pinfunction "B_6") (pintype "passive"))
      (node (ref "R2") (pin "2") (pinfunction "2_2") (pintype "passive"))
    )
    (net (code "48") (name "Net-(D1-C)") (class "Default")
      (node (ref "D1") (pin "4") (pinfunction "C_4") (pintype "passive"))
      (node (ref "R3") (pin "2") (pinfunction "2_2") (pintype "passive"))
    )
    (net (code "49") (name "Net-(D1-CK1)") (class "Default")
      (node (ref "D1") (pin "3") (pinfunction "CK1_3") (pintype "passive"))
      (node (ref "D1") (pin "8") (pinfunction "CK2_8") (pintype "passive"))
      (node (ref "JP4") (pin "COM") (pinfunction "2_COM") (pintype "passive"))
    )
    (net (code "50") (name "Net-(D1-D)") (class "Default")
      (node (ref "D1") (pin "2") (pinfunction "D_2") (pintype "passive"))
      (node (ref "R4") (pin "2") (pinfunction "2_2") (pintype "passive"))
    )
    (net (code "51") (name "Net-(D1-DP)") (class "Default")
      (node (ref "D1") (pin "5") (pinfunction "DP_5") (pintype "passive"))
      (node (ref "R8") (pin "1") (pinfunction "1_1") (pintype "passive"))
    )
    (net (code "52") (name "Net-(D1-E)") (class "Default")
      (node (ref "D1") (pin "1") (pinfunction "E_1") (pintype "passive"))
      (node (ref "R5") (pin "2") (pinfunction "2_2") (pintype "passive"))
    )
    (net (code "53") (name "Net-(D1-F)") (class "Default")
      (node (ref "D1") (pin "9") (pinfunction "F_9") (pintype "passive"))
      (node (ref "R6") (pin "1") (pinfunction "1_1") (pintype "passive"))
    )
    (net (code "54") (name "Net-(D1-G)") (class "Default")
      (node (ref "D1") (pin "10") (pinfunction "G_10") (pintype "passive"))
      (node (ref "R7") (pin "1") (pinfunction "1_1") (pintype "passive"))
    )
    (net (code "55") (name "Net-(JP1-2)") (class "Default")
      (node (ref "JP1") (pin "COM") (pinfunction "2_COM") (pintype "passive"))
      (node (ref "SHARP_1") (pin "1") (pinfunction "1_1") (pintype "passive"))
    )
    (net (code "56") (name "Net-(JP2-2)") (class "Default")
      (node (ref "JP2") (pin "COM") (pinfunction "2_COM") (pintype "passive"))
      (node (ref "SERVO_1") (pin "3") (pinfunction "3_3") (pintype "passive"))
      (node (ref "SERVO_2") (pin "3") (pinfunction "3_3") (pintype "passive"))
      (node (ref "SERVO_3") (pin "3") (pinfunction "3_3") (pintype "passive"))
    )
    (net (code "57") (name "Net-(JP3-2)") (class "Default")
      (node (ref "JP3") (pin "COM") (pinfunction "2_COM") (pintype "passive"))
      (node (ref "LINE_FOLLOWER_HEADER") (pin "1") (pinfunction "1_1") (pintype "passive"))
    )
    (net (code "58") (name "Net-(JP5-2)") (class "Default")
      (node (ref "JP5") (pin "COM") (pinfunction "2_COM") (pintype "passive"))
      (node (ref "ULTRASONIC") (pin "1") (pinfunction "1_1") (pintype "passive"))
    )
    (net (code "59") (name "Net-(JP6-2)") (class "Default")
      (node (ref "JP6") (pin "COM") (pinfunction "2_COM") (pintype "passive"))
      (node (ref "OLED_1") (pin "2") (pinfunction "2_2") (pintype "passive"))
      (node (ref "OLED_2") (pin "2") (pinfunction "2_2") (pintype "passive"))
    )
    (net (code "60") (name "Net-(JP8-2)") (class "Default")
      (node (ref "JP8") (pin "COM") (pinfunction "2_COM") (pintype "passive"))
      (node (ref "SHARP_2") (pin "1") (pinfunction "1_1") (pintype "passive"))
    )
    (net (code "61") (name "Net-(JP9-2)") (class "Default")
      (node (ref "JP9") (pin "COM") (pinfunction "2_COM") (pintype "passive"))
      (node (ref "SHARP_3") (pin "1") (pinfunction "1_1") (pintype "passive"))
    )
    (net (code "62") (name "Net-(JP10-2)") (class "Default")
      (node (ref "JP10") (pin "COM") (pinfunction "2_COM") (pintype "passive"))
      (node (ref "SHARP_4") (pin "1") (pinfunction "1_1") (pintype "passive"))
    )
    (net (code "63") (name "Net-(JP11-2)") (class "Default")
      (node (ref "JP11") (pin "COM") (pinfunction "2_COM") (pintype "passive"))
      (node (ref "OLED_1") (pin "1") (pinfunction "1_1") (pintype "passive"))
      (node (ref "OLED_2") (pin "1") (pinfunction "1_1") (pintype "passive"))
    )
    (net (code "64") (name "Net-(R9-Pad2)") (class "Default")
      (node (ref "R9") (pin "2") (pinfunction "2_2") (pintype "passive"))
      (node (ref "T1") (pin "B") (pinfunction "B_B") (pintype "passive"))
    )
    (net (code "65") (name "Net-(R11-Pad2)") (class "Default")
      (node (ref "R11") (pin "2") (pinfunction "2_2") (pintype "passive"))
      (node (ref "R12") (pin "1") (pinfunction "1_1") (pintype "passive"))
    )
    (net (code "66") (name "OC0A") (class "Default")
      (node (ref "EYFI_MEGA") (pin "47") (pinfunction "OC0A_47") (pintype "bidirectional"))
      (node (ref "PWM1") (pin "6") (pinfunction "6_6") (pintype "passive"))
    )
    (net (code "67") (name "OC0B") (class "Default")
      (node (ref "EYFI_MEGA") (pin "46") (pinfunction "OC0B_46") (pintype "bidirectional"))
      (node (ref "PWM1") (pin "7") (pinfunction "7_7") (pintype "passive"))
    )
    (net (code "68") (name "OC1A") (class "Default")
      (node (ref "EYFI_MEGA") (pin "44") (pinfunction "OC1A_44") (pintype "bidirectional"))
      (node (ref "PWM2") (pin "3") (pinfunction "3_3") (pintype "passive"))
    )
    (net (code "69") (name "OC1B") (class "Default")
      (node (ref "ARDU_CAM") (pin "7") (pinfunction "7_7") (pintype "passive"))
      (node (ref "EYFI_MEGA") (pin "45") (pinfunction "OC1B_45") (pintype "bidirectional"))
      (node (ref "PWM1") (pin "8") (pinfunction "8_8") (pintype "passive"))
    )
    (net (code "70") (name "OC2A") (class "Default")
      (node (ref "EYFI_MEGA") (pin "43") (pinfunction "OC2A_43") (pintype "bidirectional"))
      (node (ref "PWM2") (pin "4") (pinfunction "4_4") (pintype "passive"))
    )
    (net (code "71") (name "OC2B") (class "Default")
      (node (ref "EYFI_MEGA") (pin "42") (pinfunction "OC2B_42") (pintype "bidirectional"))
      (node (ref "PWM2") (pin "5") (pinfunction "5_5") (pintype "passive"))
      (node (ref "R10") (pin "2") (pinfunction "2_2") (pintype "passive"))
    )
    (net (code "72") (name "OC3A") (class "Default")
      (node (ref "EYFI_MEGA") (pin "38") (pinfunction "OC3A_38") (pintype "bidirectional"))
      (node (ref "PWM2") (pin "9") (pinfunction "9_9") (pintype "passive"))
      (node (ref "R9") (pin "1") (pinfunction "1_1") (pintype "passive"))
    )
    (net (code "73") (name "OC4A") (class "Default")
      (node (ref "EYFI_MEGA") (pin "39") (pinfunction "OC4A_39") (pintype "bidirectional"))
      (node (ref "PWM2") (pin "8") (pinfunction "8_8") (pintype "passive"))
      (node (ref "SERVO_1") (pin "2") (pinfunction "2_2") (pintype "passive"))
    )
    (net (code "74") (name "OC4B") (class "Default")
      (node (ref "EYFI_MEGA") (pin "40") (pinfunction "OC4B_40") (pintype "bidirectional"))
      (node (ref "PWM2") (pin "7") (pinfunction "7_7") (pintype "passive"))
      (node (ref "SERVO_2") (pin "2") (pinfunction "2_2") (pintype "passive"))
    )
    (net (code "75") (name "OC4C") (class "Default")
      (node (ref "EYFI_MEGA") (pin "41") (pinfunction "OC4C_41") (pintype "bidirectional"))
      (node (ref "PWM2") (pin "6") (pinfunction "6_6") (pintype "passive"))
      (node (ref "SERVO_3") (pin "2") (pinfunction "2_2") (pintype "passive"))
    )
    (net (code "76") (name "OC5A") (class "Default")
      (node (ref "EYFI_MEGA") (pin "48") (pinfunction "OC5A_48") (pintype "bidirectional"))
      (node (ref "MTR_CTR") (pin "5") (pinfunction "5_5") (pintype "passive"))
      (node (ref "PWM1") (pin "5") (pinfunction "5_5") (pintype "passive"))
    )
    (net (code "77") (name "OC5B") (class "Default")
      (node (ref "EYFI_MEGA") (pin "49") (pinfunction "OC5B_49") (pintype "bidirectional"))
      (node (ref "MTR_CTR") (pin "6") (pinfunction "6_6") (pintype "passive"))
      (node (ref "PWM1") (pin "4") (pinfunction "4_4") (pintype "passive"))
    )
    (net (code "78") (name "OC5C") (class "Default")
      (node (ref "EYFI_MEGA") (pin "50") (pinfunction "OC5C_50") (pintype "bidirectional"))
      (node (ref "PWM1") (pin "3") (pinfunction "3_3") (pintype "passive"))
    )
    (net (code "79") (name "PA0") (class "Default")
      (node (ref "ARDU_CAM") (pin "16") (pinfunction "16_16") (pintype "passive"))
      (node (ref "EYFI_MEGA") (pin "102") (pinfunction "PA0_102") (pintype "bidirectional"))
      (node (ref "GPIO2") (pin "3") (pinfunction "3_3") (pintype "passive"))
    )
    (net (code "80") (name "PA1") (class "Default")
      (node (ref "ARDU_CAM") (pin "15") (pinfunction "15_15") (pintype "passive"))
      (node (ref "EYFI_MEGA") (pin "101") (pinfunction "PA1_101") (pintype "bidirectional"))
      (node (ref "GPIO2") (pin "4") (pinfunction "4_4") (pintype "passive"))
    )
    (net (code "81") (name "PA2") (class "Default")
      (node (ref "ARDU_CAM") (pin "14") (pinfunction "14_14") (pintype "passive"))
      (node (ref "EYFI_MEGA") (pin "100") (pinfunction "PA2_100") (pintype "bidirectional"))
      (node (ref "GPIO2") (pin "5") (pinfunction "5_5") (pintype "passive"))
    )
    (net (code "82") (name "PA3") (class "Default")
      (node (ref "ARDU_CAM") (pin "13") (pinfunction "13_13") (pintype "passive"))
      (node (ref "EYFI_MEGA") (pin "99") (pinfunction "PA3_99") (pintype "bidirectional"))
      (node (ref "GPIO2") (pin "6") (pinfunction "6_6") (pintype "passive"))
    )
    (net (code "83") (name "PA4") (class "Default")
      (node (ref "ARDU_CAM") (pin "12") (pinfunction "12_12") (pintype "passive"))
      (node (ref "EYFI_MEGA") (pin "98") (pinfunction "PA4_98") (pintype "bidirectional"))
      (node (ref "GPIO2") (pin "7") (pinfunction "7_7") (pintype "passive"))
    )
    (net (code "84") (name "PA5") (class "Default")
      (node (ref "ARDU_CAM") (pin "11") (pinfunction "11_11") (pintype "passive"))
      (node (ref "EYFI_MEGA") (pin "97") (pinfunction "PA5_97") (pintype "bidirectional"))
      (node (ref "GPIO2") (pin "8") (pinfunction "8_8") (pintype "passive"))
    )
    (net (code "85") (name "PA6") (class "Default")
      (node (ref "ARDU_CAM") (pin "10") (pinfunction "10_10") (pintype "passive"))
      (node (ref "EYFI_MEGA") (pin "96") (pinfunction "PA6_96") (pintype "bidirectional"))
      (node (ref "GPIO2") (pin "9") (pinfunction "9_9") (pintype "passive"))
    )
    (net (code "86") (name "PA7") (class "Default")
      (node (ref "ARDU_CAM") (pin "9") (pinfunction "9_9") (pintype "passive"))
      (node (ref "EYFI_MEGA") (pin "95") (pinfunction "PA7_95") (pintype "bidirectional"))
      (node (ref "GPIO2") (pin "10") (pinfunction "10_10") (pintype "passive"))
    )
    (net (code "87") (name "PB1") (class "Default")
      (node (ref "EYFI_MEGA") (pin "75") (pinfunction "SCK_PB1_75") (pintype "bidirectional"))
      (node (ref "SPI1") (pin "8") (pinfunction "8_8") (pintype "passive"))
    )
    (net (code "88") (name "PB2") (class "Default")
      (node (ref "EYFI_MEGA") (pin "77") (pinfunction "MOSI_PB2_77") (pintype "bidirectional"))
      (node (ref "SPI1") (pin "6") (pinfunction "6_6") (pintype "passive"))
    )
    (net (code "89") (name "PB3") (class "Default")
      (node (ref "EYFI_MEGA") (pin "79") (pinfunction "MISO_PB3_79") (pintype "bidirectional"))
      (node (ref "SPI1") (pin "4") (pinfunction "4_4") (pintype "passive"))
    )
    (net (code "90") (name "PC0") (class "Default")
      (node (ref "EYFI_MEGA") (pin "6") (pinfunction "PC0_6") (pintype "bidirectional"))
      (node (ref "GPIO1") (pin "6") (pinfunction "6_6") (pintype "passive"))
      (node (ref "R1") (pin "1") (pinfunction "1_1") (pintype "passive"))
    )
    (net (code "91") (name "PC1") (class "Default")
      (node (ref "EYFI_MEGA") (pin "5") (pinfunction "PC1_5") (pintype "bidirectional"))
      (node (ref "GPIO1") (pin "5") (pinfunction "5_5") (pintype "passive"))
      (node (ref "R2") (pin "1") (pinfunction "1_1") (pintype "passive"))
    )
    (net (code "92") (name "PC2") (class "Default")
      (node (ref "EYFI_MEGA") (pin "4") (pinfunction "PC2_4") (pintype "bidirectional"))
      (node (ref "GPIO1") (pin "4") (pinfunction "4_4") (pintype "passive"))
      (node (ref "R3") (pin "1") (pinfunction "1_1") (pintype "passive"))
    )
    (net (code "93") (name "PC3") (class "Default")
      (node (ref "EYFI_MEGA") (pin "3") (pinfunction "PC3_3") (pintype "bidirectional"))
      (node (ref "GPIO1") (pin "3") (pinfunction "3_3") (pintype "passive"))
      (node (ref "R4") (pin "1") (pinfunction "1_1") (pintype "passive"))
    )
    (net (code "94") (name "PC4") (class "Default")
      (node (ref "EYFI_MEGA") (pin "85") (pinfunction "PC4_85") (pintype "bidirectional"))
      (node (ref "GPIO2") (pin "20") (pinfunction "20_20") (pintype "passive"))
      (node (ref "R5") (pin "1") (pinfunction "1_1") (pintype "passive"))
    )
    (net (code "95") (name "PC5") (class "Default")
      (node (ref "EYFI_MEGA") (pin "86") (pinfunction "PC5_86") (pintype "bidirectional"))
      (node (ref "GPIO2") (pin "19") (pinfunction "19_19") (pintype "passive"))
      (node (ref "R6") (pin "2") (pinfunction "2_2") (pintype "passive"))
    )
    (net (code "96") (name "PC6") (class "Default")
      (node (ref "EYFI_MEGA") (pin "87") (pinfunction "PC6_87") (pintype "bidirectional"))
      (node (ref "GPIO2") (pin "18") (pinfunction "18_18") (pintype "passive"))
      (node (ref "R7") (pin "2") (pinfunction "2_2") (pintype "passive"))
    )
    (net (code "97") (name "PC7") (class "Default")
      (node (ref "EYFI_MEGA") (pin "88") (pinfunction "PC7_88") (pintype "bidirectional"))
      (node (ref "GPIO2") (pin "17") (pinfunction "17_17") (pintype "passive"))
      (node (ref "R8") (pin "2") (pinfunction "2_2") (pintype "passive"))
    )
    (net (code "98") (name "PD0") (class "Default")
      (node (ref "EYFI_MEGA") (pin "107") (pinfunction "SCL_PD0_107") (pintype "bidirectional"))
      (node (ref "I2C") (pin "6") (pinfunction "6_6") (pintype "passive"))
    )
    (net (code "99") (name "PD1") (class "Default")
      (node (ref "EYFI_MEGA") (pin "109") (pinfunction "SDA_PD1_109") (pintype "bidirectional"))
      (node (ref "I2C") (pin "4") (pinfunction "4_4") (pintype "passive"))
    )
    (net (code "100") (name "PD4") (class "Default")
      (node (ref "EYFI_MEGA") (pin "12") (pinfunction "PD4_12") (pintype "bidirectional"))
      (node (ref "GPIO1") (pin "12") (pinfunction "12_12") (pintype "passive"))
      (node (ref "MTR_CTR") (pin "1") (pinfunction "1_1") (pintype "passive"))
    )
    (net (code "101") (name "PD5") (class "Default")
      (node (ref "EYFI_MEGA") (pin "11") (pinfunction "PD5_11") (pintype "bidirectional"))
      (node (ref "GPIO1") (pin "11") (pinfunction "11_11") (pintype "passive"))
      (node (ref "MTR_CTR") (pin "2") (pinfunction "2_2") (pintype "passive"))
    )
    (net (code "102") (name "PD6") (class "Default")
      (node (ref "EYFI_MEGA") (pin "10") (pinfunction "PD6_10") (pintype "bidirectional"))
      (node (ref "GPIO1") (pin "10") (pinfunction "10_10") (pintype "passive"))
      (node (ref "MTR_CTR") (pin "3") (pinfunction "3_3") (pintype "passive"))
    )
    (net (code "103") (name "PD7") (class "Default")
      (node (ref "EYFI_MEGA") (pin "9") (pinfunction "PD7_9") (pintype "bidirectional"))
      (node (ref "GPIO1") (pin "9") (pinfunction "9_9") (pintype "passive"))
      (node (ref "MTR_CTR") (pin "4") (pinfunction "4_4") (pintype "passive"))
    )
    (net (code "104") (name "PE2") (class "Default")
      (node (ref "EYFI_MEGA") (pin "20") (pinfunction "PE2_20") (pintype "bidirectional"))
      (node (ref "GPIO1") (pin "20") (pinfunction "20_20") (pintype "passive"))
    )
    (net (code "105") (name "PG0") (class "Default")
      (node (ref "EYFI_MEGA") (pin "8") (pinfunction "PG0_8") (pintype "bidirectional"))
      (node (ref "GPIO1") (pin "8") (pinfunction "8_8") (pintype "passive"))
    )
    (net (code "106") (name "PG1") (class "Default")
      (node (ref "EYFI_MEGA") (pin "7") (pinfunction "PG1_7") (pintype "bidirectional"))
      (node (ref "GPIO1") (pin "7") (pinfunction "7_7") (pintype "passive"))
    )
    (net (code "107") (name "PG2") (class "Default")
      (node (ref "EYFI_MEGA") (pin "94") (pinfunction "PG2_94") (pintype "bidirectional"))
      (node (ref "GPIO2") (pin "11") (pinfunction "11_11") (pintype "passive"))
      (node (ref "ULTRASONIC") (pin "2") (pinfunction "2_2") (pintype "passive"))
    )
    (net (code "108") (name "PH2") (class "Default")
      (node (ref "EYFI_MEGA") (pin "19") (pinfunction "PH2_19") (pintype "bidirectional"))
      (node (ref "GPIO1") (pin "19") (pinfunction "19_19") (pintype "passive"))
    )
    (net (code "109") (name "PH7") (class "Default")
      (node (ref "EYFI_MEGA") (pin "18") (pinfunction "PH7_18") (pintype "bidirectional"))
      (node (ref "GPIO1") (pin "18") (pinfunction "18_18") (pintype "passive"))
    )
    (net (code "110") (name "PJ2") (class "Default")
      (node (ref "EYFI_MEGA") (pin "89") (pinfunction "PJ2_89") (pintype "bidirectional"))
      (node (ref "GPIO2") (pin "16") (pinfunction "16_16") (pintype "passive"))
    )
    (net (code "111") (name "PJ3") (class "Default")
      (node (ref "EYFI_MEGA") (pin "90") (pinfunction "PJ3_90") (pintype "bidirectional"))
      (node (ref "GPIO2") (pin "15") (pinfunction "15_15") (pintype "passive"))
    )
    (net (code "112") (name "PJ4") (class "Default")
      (node (ref "EYFI_MEGA") (pin "91") (pinfunction "PJ4_91") (pintype "bidirectional"))
      (node (ref "GPIO2") (pin "14") (pinfunction "14_14") (pintype "passive"))
    )
    (net (code "113") (name "PJ5") (class "Default")
      (node (ref "EYFI_MEGA") (pin "92") (pinfunction "PJ5_92") (pintype "bidirectional"))
      (node (ref "GPIO2") (pin "13") (pinfunction "13_13") (pintype "passive"))
    )
    (net (code "114") (name "PJ6") (class "Default")
      (node (ref "EYFI_MEGA") (pin "93") (pinfunction "PJ6_93") (pintype "bidirectional"))
      (node (ref "GPIO2") (pin "12") (pinfunction "12_12") (pintype "passive"))
      (node (ref "ULTRASONIC") (pin "3") (pinfunction "3_3") (pintype "passive"))
    )
    (net (code "115") (name "PL0") (class "Default")
      (node (ref "EYFI_MEGA") (pin "17") (pinfunction "PL0_17") (pintype "bidirectional"))
      (node (ref "GPIO1") (pin "17") (pinfunction "17_17") (pintype "passive"))
    )
    (net (code "116") (name "PL1") (class "Default")
      (node (ref "EYFI_MEGA") (pin "16") (pinfunction "PL1_16") (pintype "bidirectional"))
      (node (ref "GPIO1") (pin "16") (pinfunction "16_16") (pintype "passive"))
    )
    (net (code "117") (name "PL2") (class "Default")
      (node (ref "EYFI_MEGA") (pin "15") (pinfunction "PL2_15") (pintype "bidirectional"))
      (node (ref "GPIO1") (pin "15") (pinfunction "15_15") (pintype "passive"))
    )
    (net (code "118") (name "PL6") (class "Default")
      (node (ref "EYFI_MEGA") (pin "14") (pinfunction "PL6_14") (pintype "bidirectional"))
      (node (ref "GPIO1") (pin "14") (pinfunction "14_14") (pintype "passive"))
    )
    (net (code "119") (name "PL7") (class "Default")
      (node (ref "EYFI_MEGA") (pin "13") (pinfunction "PL7_13") (pintype "bidirectional"))
      (node (ref "GPIO1") (pin "13") (pinfunction "13_13") (pintype "passive"))
    )
    (net (code "120") (name "RST") (class "Default")
      (node (ref "EYFI_MEGA") (pin "37") (pinfunction "RESET_37") (pintype "bidirectional"))
      (node (ref "PWM2") (pin "10") (pinfunction "10_10") (pintype "passive"))
    )
    (net (code "121") (name "RX1") (class "Default")
      (node (ref "ARDU_CAM") (pin "5") (pinfunction "5_5") (pintype "passive"))
      (node (ref "EYFI_MEGA") (pin "29") (pinfunction "RX1_29") (pintype "bidirectional"))
      (node (ref "UART") (pin "7") (pinfunction "7_7") (pintype "passive"))
    )
    (net (code "122") (name "RX2") (class "Default")
      (node (ref "EYFI_MEGA") (pin "27") (pinfunction "RX2_27") (pintype "bidirectional"))
      (node (ref "UART") (pin "5") (pinfunction "5_5") (pintype "passive"))
    )
    (net (code "123") (name "RX3") (class "Default")
      (node (ref "EYFI_MEGA") (pin "25") (pinfunction "RX3_25") (pintype "bidirectional"))
      (node (ref "UART") (pin "3") (pinfunction "3_3") (pintype "passive"))
    )
    (net (code "124") (name "SCK") (class "Default")
      (node (ref "EYFI_MEGA") (pin "76") (pinfunction "SCK_PB1_76") (pintype "bidirectional"))
      (node (ref "SPI1") (pin "7") (pinfunction "7_7") (pintype "passive"))
    )
    (net (code "125") (name "SCL") (class "Default")
      (node (ref "ARDU_CAM") (pin "3") (pinfunction "3_3") (pintype "passive"))
      (node (ref "EYFI_MEGA") (pin "108") (pinfunction "SCL_PD0_108") (pintype "bidirectional"))
      (node (ref "GY-87") (pin "4") (pinfunction "4_4") (pintype "passive"))
      (node (ref "I2C") (pin "5") (pinfunction "5_5") (pintype "passive"))
      (node (ref "I2C1") (pin "3") (pinfunction "3_3") (pintype "passive"))
      (node (ref "I2C2") (pin "3") (pinfunction "3_3") (pintype "passive"))
      (node (ref "LINE_FOLLOWER_HEADER") (pin "3") (pinfunction "3_3") (pintype "passive"))
      (node (ref "OLED_1") (pin "3") (pinfunction "3_3") (pintype "passive"))
      (node (ref "OLED_2") (pin "3") (pinfunction "3_3") (pintype "passive"))
    )
    (net (code "126") (name "SDA") (class "Default")
      (node (ref "ARDU_CAM") (pin "4") (pinfunction "4_4") (pintype "passive"))
      (node (ref "EYFI_MEGA") (pin "110") (pinfunction "SDA_PD1_110") (pintype "bidirectional"))
      (node (ref "GY-87") (pin "5") (pinfunction "5_5") (pintype "passive"))
      (node (ref "I2C") (pin "3") (pinfunction "3_3") (pintype "passive"))
      (node (ref "I2C1") (pin "2") (pinfunction "2_2") (pintype "passive"))
      (node (ref "I2C2") (pin "2") (pinfunction "2_2") (pintype "passive"))
      (node (ref "LINE_FOLLOWER_HEADER") (pin "2") (pinfunction "2_2") (pintype "passive"))
      (node (ref "OLED_1") (pin "4") (pinfunction "4_4") (pintype "passive"))
      (node (ref "OLED_2") (pin "4") (pinfunction "4_4") (pintype "passive"))
    )
    (net (code "127") (name "SS0{slash}PB0") (class "Default")
      (node (ref "EYFI_MEGA") (pin "73") (pinfunction "SS0_PB0_73") (pintype "bidirectional"))
      (node (ref "SPI1") (pin "10") (pinfunction "10_10") (pintype "passive"))
    )
    (net (code "128") (name "SS1{slash}PJ7") (class "Default")
      (node (ref "EYFI_MEGA") (pin "74") (pinfunction "SS1_PJ7_74") (pintype "bidirectional"))
      (node (ref "SPI1") (pin "9") (pinfunction "9_9") (pintype "passive"))
    )
    (net (code "129") (name "TX1") (class "Default")
      (node (ref "EYFI_MEGA") (pin "30") (pinfunction "TX1_30") (pintype "bidirectional"))
      (node (ref "UART") (pin "8") (pinfunction "8_8") (pintype "passive"))
    )
    (net (code "130") (name "TX2") (class "Default")
      (node (ref "EYFI_MEGA") (pin "28") (pinfunction "TX2_28") (pintype "bidirectional"))
      (node (ref "UART") (pin "6") (pinfunction "6_6") (pintype "passive"))
    )
    (net (code "131") (name "TX3") (class "Default")
      (node (ref "EYFI_MEGA") (pin "26") (pinfunction "TX3_26") (pintype "bidirectional"))
      (node (ref "UART") (pin "4") (pinfunction "4_4") (pintype "passive"))
    )
    (net (code "132") (name "XCLK") (class "Default")
      (node (ref "ARDU_CAM") (pin "8") (pinfunction "8_8") (pintype "passive"))
      (node (ref "R10") (pin "1") (pinfunction "1_1") (pintype "passive"))
      (node (ref "R11") (pin "1") (pinfunction "1_1") (pintype "passive"))
    )
    (net (code "133") (name "unconnected-(ARDU_CAM-Pad6)") (class "Default")
      (node (ref "ARDU_CAM") (pin "6") (pinfunction "6_6") (pintype "passive"))
    )
    (net (code "134") (name "unconnected-(GY-87-Pad2)") (class "Default")
      (node (ref "GY-87") (pin "2") (pinfunction "2_2") (pintype "passive"))
    )
    (net (code "135") (name "unconnected-(GY-87-Pad6)") (class "Default")
      (node (ref "GY-87") (pin "6") (pinfunction "6_6") (pintype "passive"))
    )
    (net (code "136") (name "unconnected-(GY-87-Pad7)") (class "Default")
      (node (ref "GY-87") (pin "7") (pinfunction "7_7") (pintype "passive"))
    )
    (net (code "137") (name "unconnected-(GY-87-Pad8)") (class "Default")
      (node (ref "GY-87") (pin "8") (pinfunction "8_8") (pintype "passive"))
    )
    (net (code "138") (name "unconnected-(JP1-3-PadNC)") (class "Default")
      (node (ref "JP1") (pin "NC") (pinfunction "3_NC") (pintype "passive"))
    )
    (net (code "139") (name "unconnected-(JP2-3-PadNC)") (class "Default")
      (node (ref "JP2") (pin "NC") (pinfunction "3_NC") (pintype "passive"))
    )
    (net (code "140") (name "unconnected-(JP3-3-PadNC)") (class "Default")
      (node (ref "JP3") (pin "NC") (pinfunction "3_NC") (pintype "passive"))
    )
    (net (code "141") (name "unconnected-(JP4-3-PadNC)") (class "Default")
      (node (ref "JP4") (pin "NC") (pinfunction "3_NC") (pintype "passive"))
    )
    (net (code "142") (name "unconnected-(JP5-3-PadNC)") (class "Default")
      (node (ref "JP5") (pin "NC") (pinfunction "3_NC") (pintype "passive"))
    )
    (net (code "143") (name "unconnected-(JP6-3-PadNC)") (class "Default")
      (node (ref "JP6") (pin "NC") (pinfunction "3_NC") (pintype "passive"))
    )
    (net (code "144") (name "unconnected-(JP8-3-PadNC)") (class "Default")
      (node (ref "JP8") (pin "NC") (pinfunction "3_NC") (pintype "passive"))
    )
    (net (code "145") (name "unconnected-(JP9-3-PadNC)") (class "Default")
      (node (ref "JP9") (pin "NC") (pinfunction "3_NC") (pintype "passive"))
    )
    (net (code "146") (name "unconnected-(JP10-3-PadNC)") (class "Default")
      (node (ref "JP10") (pin "NC") (pinfunction "3_NC") (pintype "passive"))
    )
    (net (code "147") (name "unconnected-(JP11-3-PadNC)") (class "Default")
      (node (ref "JP11") (pin "NC") (pinfunction "3_NC") (pintype "passive"))
    )
    (net (code "148") (name "unconnected-(UART-Pad9)") (class "Default")
      (node (ref "UART") (pin "9") (pinfunction "9_9") (pintype "passive"))
    )
    (net (code "149") (name "unconnected-(UART-Pad10)") (class "Default")
      (node (ref "UART") (pin "10") (pinfunction "10_10") (pintype "passive"))
    )
  )
)
